# 477breakout.net
KiCad netlist of a schematic drawn in EAGLE
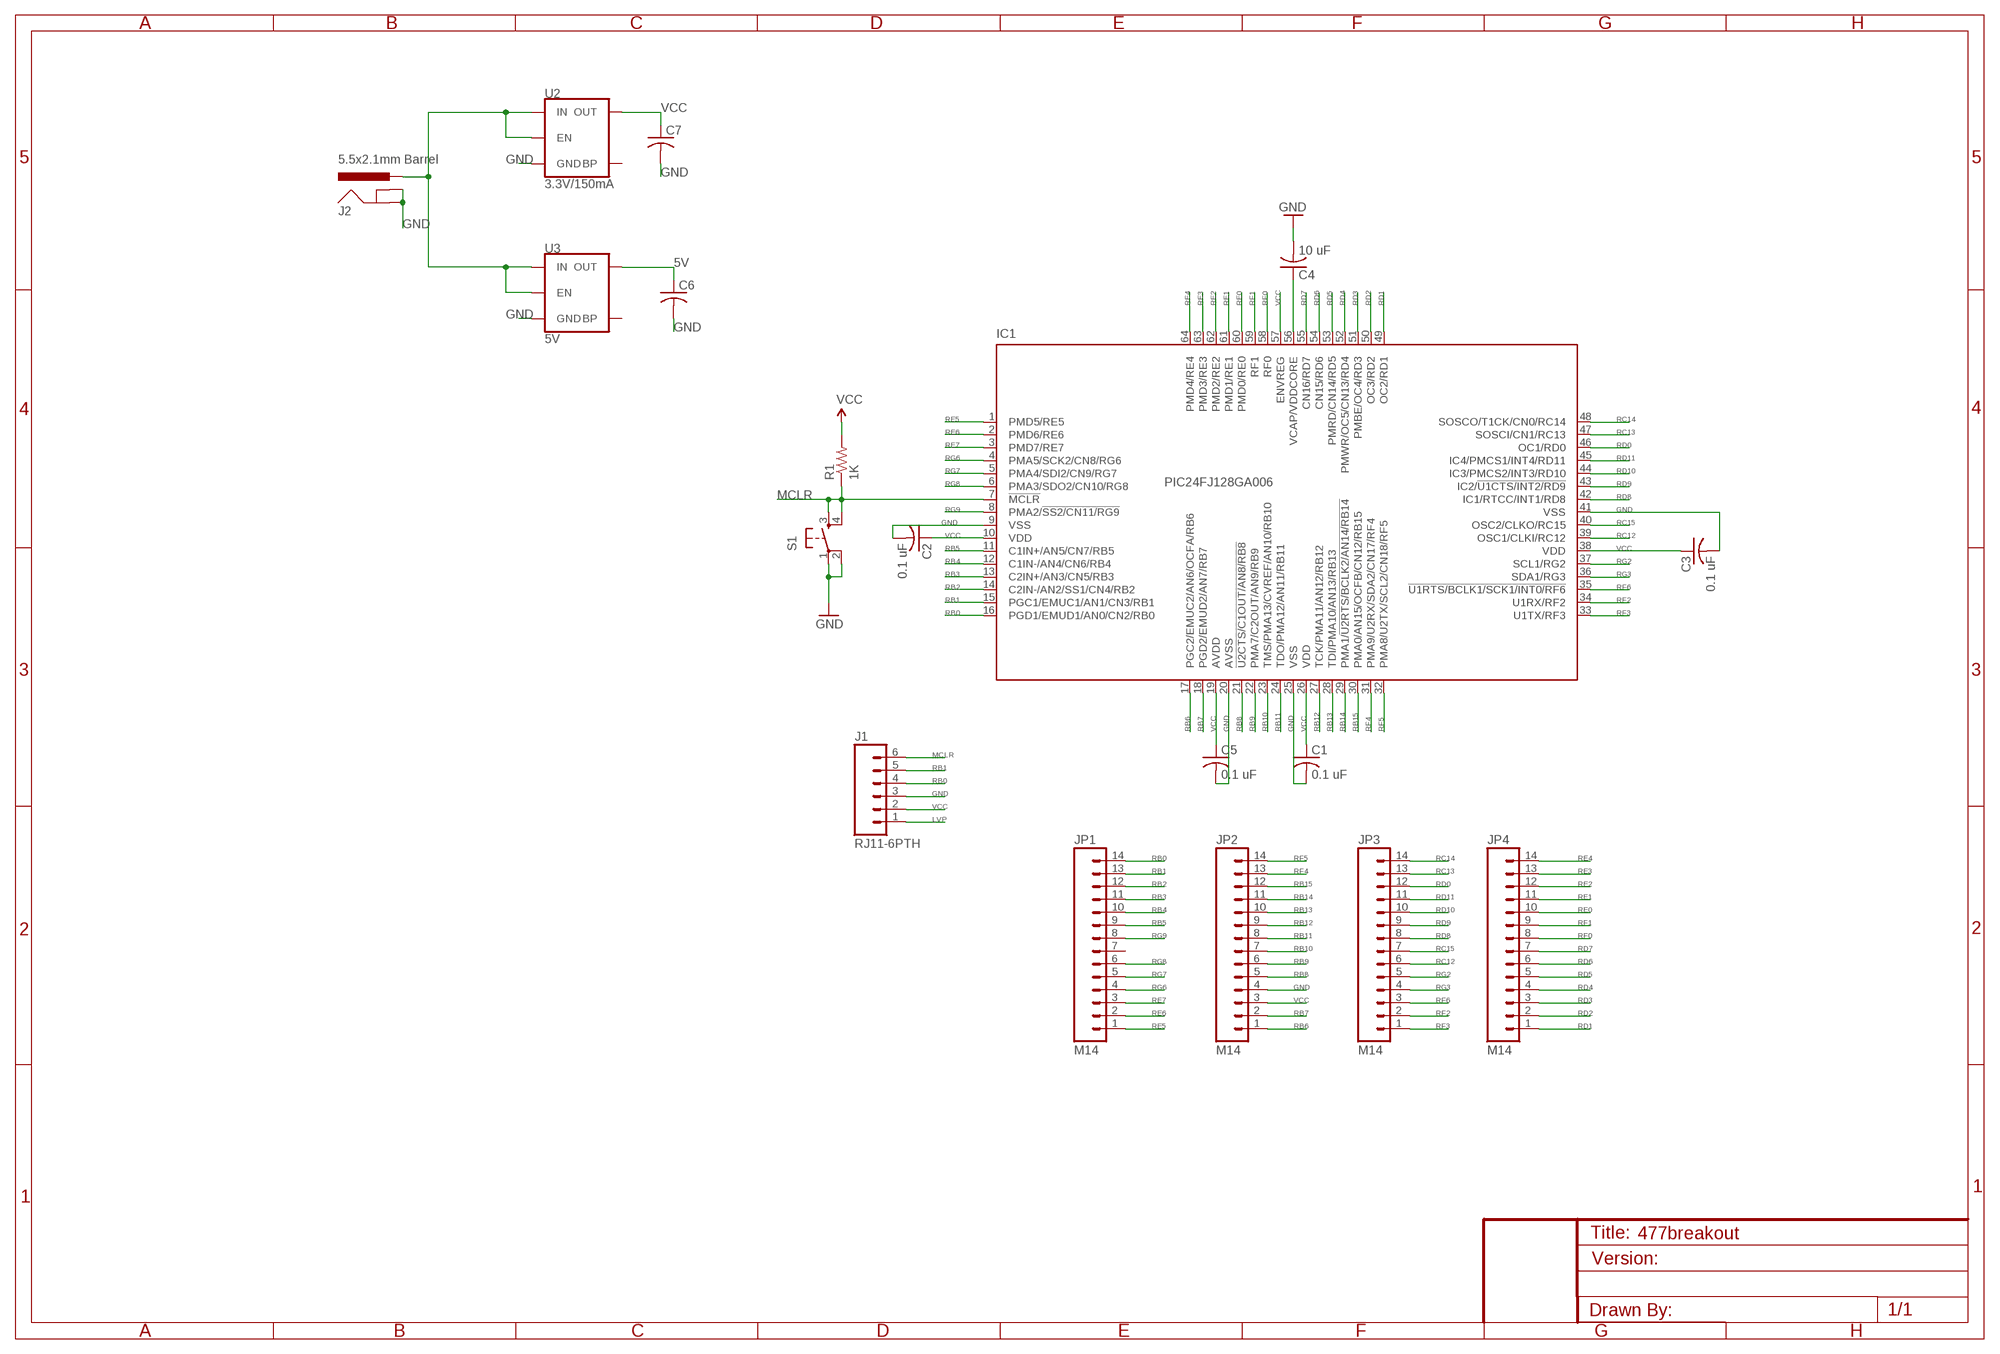
[diagram p0: schematic, sheet 1]

(export (version "E")
  (design (tool "Eeschema 10.0.6"))
  (components
    (comp (ref "C1")
      (value "0.1 uF")
      (footprint "eagle-import:C0402")
      (libsource (lib "eagle-import") (part "C-USC0402"))
    )
    (comp (ref "C2")
      (value "0.1 uF")
      (footprint "eagle-import:C0402")
      (libsource (lib "eagle-import") (part "C-USC0402"))
    )
    (comp (ref "C3")
      (value "0.1 uF")
      (footprint "eagle-import:C0402")
      (libsource (lib "eagle-import") (part "C-USC0402"))
    )
    (comp (ref "C4")
      (value "10 uF")
      (footprint "eagle-import:C0805")
      (libsource (lib "eagle-import") (part "C-USC0805"))
    )
    (comp (ref "C5")
      (value "0.1 uF")
      (footprint "eagle-import:C0402")
      (libsource (lib "eagle-import") (part "C-USC0402"))
    )
    (comp (ref "C6")
      (value "C-USC1206")
      (footprint "eagle-import:C1206")
      (libsource (lib "eagle-import") (part "C-USC1206"))
    )
    (comp (ref "C7")
      (value "C-USC1206")
      (footprint "eagle-import:C1206")
      (libsource (lib "eagle-import") (part "C-USC1206"))
    )
    (comp (ref "IC1")
      (value "PIC24FJ128GA006")
      (footprint "eagle-import:TQFP64-10X10")
      (fields (field (name "MF") "MICROCHIP") (field (name "MPN") "PIC24FJ128GA006-I/PT"))
      (libsource (lib "eagle-import") (part "PIC24FJGA006128"))
    )
    (comp (ref "J1")
      (value "RJ11-6PTH")
      (footprint "eagle-import:RJ11-6")
      (libsource (lib "eagle-import") (part "RJ11-6PTH"))
    )
    (comp (ref "J2")
      (value "5.5x2.1mm Barrel")
      (footprint "eagle-import:POWER_JACK_SMD")
      (libsource (lib "eagle-import") (part "POWER_JACKSMD"))
    )
    (comp (ref "JP1")
      (value "M14")
      (footprint "eagle-import:1X14")
      (libsource (lib "eagle-import") (part "M14"))
    )
    (comp (ref "JP2")
      (value "M14")
      (footprint "eagle-import:1X14")
      (libsource (lib "eagle-import") (part "M14"))
    )
    (comp (ref "JP3")
      (value "M14")
      (footprint "eagle-import:1X14")
      (libsource (lib "eagle-import") (part "M14"))
    )
    (comp (ref "JP4")
      (value "M14")
      (footprint "eagle-import:1X14")
      (libsource (lib "eagle-import") (part "M14"))
    )
    (comp (ref "R1")
      (value "1K")
      (footprint "eagle-import:0204_7")
      (libsource (lib "eagle-import") (part "R-US_0204/7"))
    )
    (comp (ref "S1")
      (value "TAC_SWITCHPTH")
      (footprint "eagle-import:TACTILE-PTH")
      (libsource (lib "eagle-import") (part "TAC_SWITCHPTH"))
    )
    (comp (ref "U2")
      (value "3.3V/150mA")
      (footprint "eagle-import:SOT23-5")
      (libsource (lib "eagle-import") (part "V_REG_MIC52053.3V"))
    )
    (comp (ref "U3")
      (value "5V")
      (footprint "eagle-import:SOT23-5")
      (libsource (lib "eagle-import") (part "V_REG_MIC52055V"))
    )
  )
  (nets
    (net (code "1") (name "/5V") (class "Default")
      (node (ref "C6") (pin "1") (pinfunction "1_1") (pintype "passive"))
      (node (ref "U3") (pin "5") (pinfunction "OUT_5") (pintype "passive"))
    )
    (net (code "2") (name "/LVP") (class "Default")
      (node (ref "J1") (pin "1") (pinfunction "1_1") (pintype "passive"))
    )
    (net (code "3") (name "/MCLR") (class "Default")
      (node (ref "IC1") (pin "7") (pinfunction "~{MCLR}_7") (pintype "bidirectional"))
      (node (ref "J1") (pin "6") (pinfunction "6_6") (pintype "passive"))
      (node (ref "R1") (pin "1") (pinfunction "1_1") (pintype "passive"))
      (node (ref "S1") (pin "3") (pinfunction "3_3") (pintype "passive"))
      (node (ref "S1") (pin "4") (pinfunction "4_4") (pintype "passive"))
    )
    (net (code "4") (name "/RB0") (class "Default")
      (node (ref "IC1") (pin "16") (pinfunction "PGD1/EMUD1/AN0/CN2/RB0_16") (pintype "bidirectional"))
      (node (ref "J1") (pin "4") (pinfunction "4_4") (pintype "passive"))
      (node (ref "JP1") (pin "14") (pinfunction "14_14") (pintype "passive"))
    )
    (net (code "5") (name "/RB1") (class "Default")
      (node (ref "IC1") (pin "15") (pinfunction "PGC1/EMUC1/AN1/CN3/RB1_15") (pintype "bidirectional"))
      (node (ref "J1") (pin "5") (pinfunction "5_5") (pintype "passive"))
      (node (ref "JP1") (pin "13") (pinfunction "13_13") (pintype "passive"))
    )
    (net (code "6") (name "/RB2") (class "Default")
      (node (ref "IC1") (pin "14") (pinfunction "C2IN-/AN2/SS1/CN4/RB2_14") (pintype "bidirectional"))
      (node (ref "JP1") (pin "12") (pinfunction "12_12") (pintype "passive"))
    )
    (net (code "7") (name "/RB3") (class "Default")
      (node (ref "IC1") (pin "13") (pinfunction "C2IN+/AN3/CN5/RB3_13") (pintype "bidirectional"))
      (node (ref "JP1") (pin "11") (pinfunction "11_11") (pintype "passive"))
    )
    (net (code "8") (name "/RB4") (class "Default")
      (node (ref "IC1") (pin "12") (pinfunction "C1IN-/AN4/CN6/RB4_12") (pintype "bidirectional"))
      (node (ref "JP1") (pin "10") (pinfunction "10_10") (pintype "passive"))
    )
    (net (code "9") (name "/RB5") (class "Default")
      (node (ref "IC1") (pin "11") (pinfunction "C1IN+/AN5/CN7/RB5_11") (pintype "bidirectional"))
      (node (ref "JP1") (pin "9") (pinfunction "9_9") (pintype "passive"))
    )
    (net (code "10") (name "/RB6") (class "Default")
      (node (ref "IC1") (pin "17") (pinfunction "PGC2/EMUC2/AN6/OCFA/RB6_17") (pintype "bidirectional"))
      (node (ref "JP2") (pin "1") (pinfunction "1_1") (pintype "passive"))
    )
    (net (code "11") (name "/RB7") (class "Default")
      (node (ref "IC1") (pin "18") (pinfunction "PGD2/EMUD2/AN7/RB7_18") (pintype "bidirectional"))
      (node (ref "JP2") (pin "2") (pinfunction "2_2") (pintype "passive"))
    )
    (net (code "12") (name "/RB8") (class "Default")
      (node (ref "IC1") (pin "21") (pinfunction "~{U2CTS/C1OUT/AN8/RB8}_21") (pintype "bidirectional"))
      (node (ref "JP2") (pin "5") (pinfunction "5_5") (pintype "passive"))
    )
    (net (code "13") (name "/RB9") (class "Default")
      (node (ref "IC1") (pin "22") (pinfunction "PMA7/C2OUT/AN9/RB9_22") (pintype "bidirectional"))
      (node (ref "JP2") (pin "6") (pinfunction "6_6") (pintype "passive"))
    )
    (net (code "14") (name "/RB10") (class "Default")
      (node (ref "IC1") (pin "23") (pinfunction "TMS/PMA13/CVREF/AN10/RB10_23") (pintype "bidirectional"))
      (node (ref "JP2") (pin "7") (pinfunction "7_7") (pintype "passive"))
    )
    (net (code "15") (name "/RB11") (class "Default")
      (node (ref "IC1") (pin "24") (pinfunction "TDO/PMA12/AN11/RB11_24") (pintype "bidirectional"))
      (node (ref "JP2") (pin "8") (pinfunction "8_8") (pintype "passive"))
    )
    (net (code "16") (name "/RB12") (class "Default")
      (node (ref "IC1") (pin "27") (pinfunction "TCK/PMA11/AN12/RB12_27") (pintype "bidirectional"))
      (node (ref "JP2") (pin "9") (pinfunction "9_9") (pintype "passive"))
    )
    (net (code "17") (name "/RB13") (class "Default")
      (node (ref "IC1") (pin "28") (pinfunction "TDI/PMA10/AN13/RB13_28") (pintype "bidirectional"))
      (node (ref "JP2") (pin "10") (pinfunction "10_10") (pintype "passive"))
    )
    (net (code "18") (name "/RB14") (class "Default")
      (node (ref "IC1") (pin "29") (pinfunction "PMA1/~{U2RTS/BCLK2/AN14/RB14}_29") (pintype "bidirectional"))
      (node (ref "JP2") (pin "11") (pinfunction "11_11") (pintype "passive"))
    )
    (net (code "19") (name "/RB15") (class "Default")
      (node (ref "IC1") (pin "30") (pinfunction "PMA0/AN15/OCFB/CN12/RB15_30") (pintype "bidirectional"))
      (node (ref "JP2") (pin "12") (pinfunction "12_12") (pintype "passive"))
    )
    (net (code "20") (name "/RC12") (class "Default")
      (node (ref "IC1") (pin "39") (pinfunction "OSC1/CLKI/RC12_39") (pintype "bidirectional"))
      (node (ref "JP3") (pin "6") (pinfunction "6_6") (pintype "passive"))
    )
    (net (code "21") (name "/RC13") (class "Default")
      (node (ref "IC1") (pin "47") (pinfunction "SOSCI/CN1/RC13_47") (pintype "bidirectional"))
      (node (ref "JP3") (pin "13") (pinfunction "13_13") (pintype "passive"))
    )
    (net (code "22") (name "/RC14") (class "Default")
      (node (ref "IC1") (pin "48") (pinfunction "SOSCO/T1CK/CN0/RC14_48") (pintype "bidirectional"))
      (node (ref "JP3") (pin "14") (pinfunction "14_14") (pintype "passive"))
    )
    (net (code "23") (name "/RC15") (class "Default")
      (node (ref "IC1") (pin "40") (pinfunction "OSC2/CLKO/RC15_40") (pintype "bidirectional"))
      (node (ref "JP3") (pin "7") (pinfunction "7_7") (pintype "passive"))
    )
    (net (code "24") (name "/RD0") (class "Default")
      (node (ref "IC1") (pin "46") (pinfunction "OC1/RD0_46") (pintype "bidirectional"))
      (node (ref "JP3") (pin "12") (pinfunction "12_12") (pintype "passive"))
    )
    (net (code "25") (name "/RD1") (class "Default")
      (node (ref "IC1") (pin "49") (pinfunction "OC2/RD1_49") (pintype "bidirectional"))
      (node (ref "JP4") (pin "1") (pinfunction "1_1") (pintype "passive"))
    )
    (net (code "26") (name "/RD2") (class "Default")
      (node (ref "IC1") (pin "50") (pinfunction "OC3/RD2_50") (pintype "bidirectional"))
      (node (ref "JP4") (pin "2") (pinfunction "2_2") (pintype "passive"))
    )
    (net (code "27") (name "/RD3") (class "Default")
      (node (ref "IC1") (pin "51") (pinfunction "PMBE/OC4/RD3_51") (pintype "bidirectional"))
      (node (ref "JP4") (pin "3") (pinfunction "3_3") (pintype "passive"))
    )
    (net (code "28") (name "/RD4") (class "Default")
      (node (ref "IC1") (pin "52") (pinfunction "PMWR/OC5/CN13/RD4_52") (pintype "bidirectional"))
      (node (ref "JP4") (pin "4") (pinfunction "4_4") (pintype "passive"))
    )
    (net (code "29") (name "/RD5") (class "Default")
      (node (ref "IC1") (pin "53") (pinfunction "PMRD/CN14/RD5_53") (pintype "bidirectional"))
      (node (ref "JP4") (pin "5") (pinfunction "5_5") (pintype "passive"))
    )
    (net (code "30") (name "/RD6") (class "Default")
      (node (ref "IC1") (pin "54") (pinfunction "CN15/RD6_54") (pintype "bidirectional"))
      (node (ref "JP4") (pin "6") (pinfunction "6_6") (pintype "passive"))
    )
    (net (code "31") (name "/RD7") (class "Default")
      (node (ref "IC1") (pin "55") (pinfunction "CN16/RD7_55") (pintype "bidirectional"))
      (node (ref "JP4") (pin "7") (pinfunction "7_7") (pintype "passive"))
    )
    (net (code "32") (name "/RD8") (class "Default")
      (node (ref "IC1") (pin "42") (pinfunction "IC1/RTCC/INT1/RD8_42") (pintype "bidirectional"))
      (node (ref "JP3") (pin "8") (pinfunction "8_8") (pintype "passive"))
    )
    (net (code "33") (name "/RD9") (class "Default")
      (node (ref "IC1") (pin "43") (pinfunction "IC2/~{U1CTS/INT2/RD9}_43") (pintype "bidirectional"))
      (node (ref "JP3") (pin "9") (pinfunction "9_9") (pintype "passive"))
    )
    (net (code "34") (name "/RD10") (class "Default")
      (node (ref "IC1") (pin "44") (pinfunction "IC3/PMCS2/INT3/RD10_44") (pintype "bidirectional"))
      (node (ref "JP3") (pin "10") (pinfunction "10_10") (pintype "passive"))
    )
    (net (code "35") (name "/RD11") (class "Default")
      (node (ref "IC1") (pin "45") (pinfunction "IC4/PMCS1/INT4/RD11_45") (pintype "bidirectional"))
      (node (ref "JP3") (pin "11") (pinfunction "11_11") (pintype "passive"))
    )
    (net (code "36") (name "/RE0") (class "Default")
      (node (ref "IC1") (pin "60") (pinfunction "PMD0/RE0_60") (pintype "bidirectional"))
      (node (ref "JP4") (pin "10") (pinfunction "10_10") (pintype "passive"))
    )
    (net (code "37") (name "/RE1") (class "Default")
      (node (ref "IC1") (pin "61") (pinfunction "PMD1/RE1_61") (pintype "bidirectional"))
      (node (ref "JP4") (pin "11") (pinfunction "11_11") (pintype "passive"))
    )
    (net (code "38") (name "/RE2") (class "Default")
      (node (ref "IC1") (pin "62") (pinfunction "PMD2/RE2_62") (pintype "bidirectional"))
      (node (ref "JP4") (pin "12") (pinfunction "12_12") (pintype "passive"))
    )
    (net (code "39") (name "/RE3") (class "Default")
      (node (ref "IC1") (pin "63") (pinfunction "PMD3/RE3_63") (pintype "bidirectional"))
      (node (ref "JP4") (pin "13") (pinfunction "13_13") (pintype "passive"))
    )
    (net (code "40") (name "/RE4") (class "Default")
      (node (ref "IC1") (pin "64") (pinfunction "PMD4/RE4_64") (pintype "bidirectional"))
      (node (ref "JP4") (pin "14") (pinfunction "14_14") (pintype "passive"))
    )
    (net (code "41") (name "/RE5") (class "Default")
      (node (ref "IC1") (pin "1") (pinfunction "PMD5/RE5_1") (pintype "bidirectional"))
      (node (ref "JP1") (pin "1") (pinfunction "1_1") (pintype "passive"))
    )
    (net (code "42") (name "/RE6") (class "Default")
      (node (ref "IC1") (pin "2") (pinfunction "PMD6/RE6_2") (pintype "bidirectional"))
      (node (ref "JP1") (pin "2") (pinfunction "2_2") (pintype "passive"))
    )
    (net (code "43") (name "/RE7") (class "Default")
      (node (ref "IC1") (pin "3") (pinfunction "PMD7/RE7_3") (pintype "bidirectional"))
      (node (ref "JP1") (pin "3") (pinfunction "3_3") (pintype "passive"))
    )
    (net (code "44") (name "/RF0") (class "Default")
      (node (ref "IC1") (pin "58") (pinfunction "RF0_58") (pintype "bidirectional"))
      (node (ref "JP4") (pin "8") (pinfunction "8_8") (pintype "passive"))
    )
    (net (code "45") (name "/RF1") (class "Default")
      (node (ref "IC1") (pin "59") (pinfunction "RF1_59") (pintype "bidirectional"))
      (node (ref "JP4") (pin "9") (pinfunction "9_9") (pintype "passive"))
    )
    (net (code "46") (name "/RF2") (class "Default")
      (node (ref "IC1") (pin "34") (pinfunction "U1RX/RF2_34") (pintype "bidirectional"))
      (node (ref "JP3") (pin "2") (pinfunction "2_2") (pintype "passive"))
    )
    (net (code "47") (name "/RF3") (class "Default")
      (node (ref "IC1") (pin "33") (pinfunction "U1TX/RF3_33") (pintype "bidirectional"))
      (node (ref "JP3") (pin "1") (pinfunction "1_1") (pintype "passive"))
    )
    (net (code "48") (name "/RF4") (class "Default")
      (node (ref "IC1") (pin "31") (pinfunction "PMA9/U2RX/SDA2/CN17/RF4_31") (pintype "bidirectional"))
      (node (ref "JP2") (pin "13") (pinfunction "13_13") (pintype "passive"))
    )
    (net (code "49") (name "/RF5") (class "Default")
      (node (ref "IC1") (pin "32") (pinfunction "PMA8/U2TX/SCL2/CN18/RF5_32") (pintype "bidirectional"))
      (node (ref "JP2") (pin "14") (pinfunction "14_14") (pintype "passive"))
    )
    (net (code "50") (name "/RF6") (class "Default")
      (node (ref "IC1") (pin "35") (pinfunction "~{U1RTS/BCLK1/SCK1/INT0/RF6}_35") (pintype "bidirectional"))
      (node (ref "JP3") (pin "3") (pinfunction "3_3") (pintype "passive"))
    )
    (net (code "51") (name "/RG2") (class "Default")
      (node (ref "IC1") (pin "37") (pinfunction "SCL1/RG2_37") (pintype "bidirectional"))
      (node (ref "JP3") (pin "5") (pinfunction "5_5") (pintype "passive"))
    )
    (net (code "52") (name "/RG3") (class "Default")
      (node (ref "IC1") (pin "36") (pinfunction "SDA1/RG3_36") (pintype "bidirectional"))
      (node (ref "JP3") (pin "4") (pinfunction "4_4") (pintype "passive"))
    )
    (net (code "53") (name "/RG6") (class "Default")
      (node (ref "IC1") (pin "4") (pinfunction "PMA5/SCK2/CN8/RG6_4") (pintype "bidirectional"))
      (node (ref "JP1") (pin "4") (pinfunction "4_4") (pintype "passive"))
    )
    (net (code "54") (name "/RG7") (class "Default")
      (node (ref "IC1") (pin "5") (pinfunction "PMA4/SDI2/CN9/RG7_5") (pintype "bidirectional"))
      (node (ref "JP1") (pin "5") (pinfunction "5_5") (pintype "passive"))
    )
    (net (code "55") (name "/RG8") (class "Default")
      (node (ref "IC1") (pin "6") (pinfunction "PMA3/SDO2/CN10/RG8_6") (pintype "bidirectional"))
      (node (ref "JP1") (pin "6") (pinfunction "6_6") (pintype "passive"))
    )
    (net (code "56") (name "/RG9") (class "Default")
      (node (ref "IC1") (pin "8") (pinfunction "PMA2/~{SS2/CN11/RG9}_8") (pintype "bidirectional"))
      (node (ref "JP1") (pin "8") (pinfunction "8_8") (pintype "passive"))
    )
    (net (code "57") (name "GND") (class "Default")
      (node (ref "C1") (pin "2") (pinfunction "2_2") (pintype "passive"))
      (node (ref "C2") (pin "2") (pinfunction "2_2") (pintype "passive"))
      (node (ref "C3") (pin "2") (pinfunction "2_2") (pintype "passive"))
      (node (ref "C4") (pin "2") (pinfunction "2_2") (pintype "passive"))
      (node (ref "C5") (pin "2") (pinfunction "2_2") (pintype "passive"))
      (node (ref "C6") (pin "2") (pinfunction "2_2") (pintype "passive"))
      (node (ref "C7") (pin "2") (pinfunction "2_2") (pintype "passive"))
      (node (ref "IC1") (pin "20") (pinfunction "AVSS_20") (pintype "power_in"))
      (node (ref "IC1") (pin "25") (pinfunction "VSS_25") (pintype "power_in"))
      (node (ref "IC1") (pin "41") (pinfunction "VSS_41") (pintype "power_in"))
      (node (ref "IC1") (pin "9") (pinfunction "VSS_9") (pintype "power_in"))
      (node (ref "J1") (pin "3") (pinfunction "3_3") (pintype "passive"))
      (node (ref "J2") (pin "GND") (pinfunction "GNDBREAK_GND") (pintype "bidirectional"))
      (node (ref "J2") (pin "P$4") (pinfunction "GND_P$4") (pintype "bidirectional"))
      (node (ref "JP2") (pin "4") (pinfunction "4_4") (pintype "passive"))
      (node (ref "S1") (pin "1") (pinfunction "1_1") (pintype "passive"))
      (node (ref "S1") (pin "2") (pinfunction "2_2") (pintype "passive"))
      (node (ref "U2") (pin "2") (pinfunction "GND_2") (pintype "input"))
      (node (ref "U3") (pin "2") (pinfunction "GND_2") (pintype "input"))
    )
    (net (code "58") (name "Net-(IC1-VCAP{slash}VDDCORE)") (class "Default")
      (node (ref "C4") (pin "1") (pinfunction "1_1") (pintype "passive"))
      (node (ref "IC1") (pin "56") (pinfunction "VCAP/VDDCORE_56") (pintype "bidirectional"))
    )
    (net (code "59") (name "Net-(J2-PWR)") (class "Default")
      (node (ref "J2") (pin "VIN0") (pinfunction "PWR_VIN0") (pintype "bidirectional"))
      (node (ref "U2") (pin "1") (pinfunction "IN_1") (pintype "input"))
      (node (ref "U2") (pin "3") (pinfunction "EN_3") (pintype "input"))
      (node (ref "U3") (pin "1") (pinfunction "IN_1") (pintype "input"))
      (node (ref "U3") (pin "3") (pinfunction "EN_3") (pintype "input"))
    )
    (net (code "60") (name "VCC") (class "Default")
      (node (ref "C1") (pin "1") (pinfunction "1_1") (pintype "passive"))
      (node (ref "C2") (pin "1") (pinfunction "1_1") (pintype "passive"))
      (node (ref "C3") (pin "1") (pinfunction "1_1") (pintype "passive"))
      (node (ref "C5") (pin "1") (pinfunction "1_1") (pintype "passive"))
      (node (ref "C7") (pin "1") (pinfunction "1_1") (pintype "passive"))
      (node (ref "IC1") (pin "10") (pinfunction "VDD_10") (pintype "power_in"))
      (node (ref "IC1") (pin "19") (pinfunction "AVDD_19") (pintype "power_in"))
      (node (ref "IC1") (pin "26") (pinfunction "VDD_26") (pintype "power_in"))
      (node (ref "IC1") (pin "38") (pinfunction "VDD_38") (pintype "power_in"))
      (node (ref "IC1") (pin "57") (pinfunction "ENVREG_57") (pintype "bidirectional"))
      (node (ref "J1") (pin "2") (pinfunction "2_2") (pintype "passive"))
      (node (ref "JP2") (pin "3") (pinfunction "3_3") (pintype "passive"))
      (node (ref "R1") (pin "2") (pinfunction "2_2") (pintype "passive"))
      (node (ref "U2") (pin "5") (pinfunction "OUT_5") (pintype "passive"))
    )
    (net (code "61") (name "unconnected-(JP1-Pad7)") (class "Default")
      (node (ref "JP1") (pin "7") (pinfunction "7_7") (pintype "passive"))
    )
    (net (code "62") (name "unconnected-(U2-BP-Pad4)") (class "Default")
      (node (ref "U2") (pin "4") (pinfunction "BP_4") (pintype "input"))
    )
    (net (code "63") (name "unconnected-(U3-BP-Pad4)") (class "Default")
      (node (ref "U3") (pin "4") (pinfunction "BP_4") (pintype "input"))
    )
  )
)
